# Arduino_HomeMonitorv1r4-current.net
KiCad netlist of a schematic drawn in EAGLE
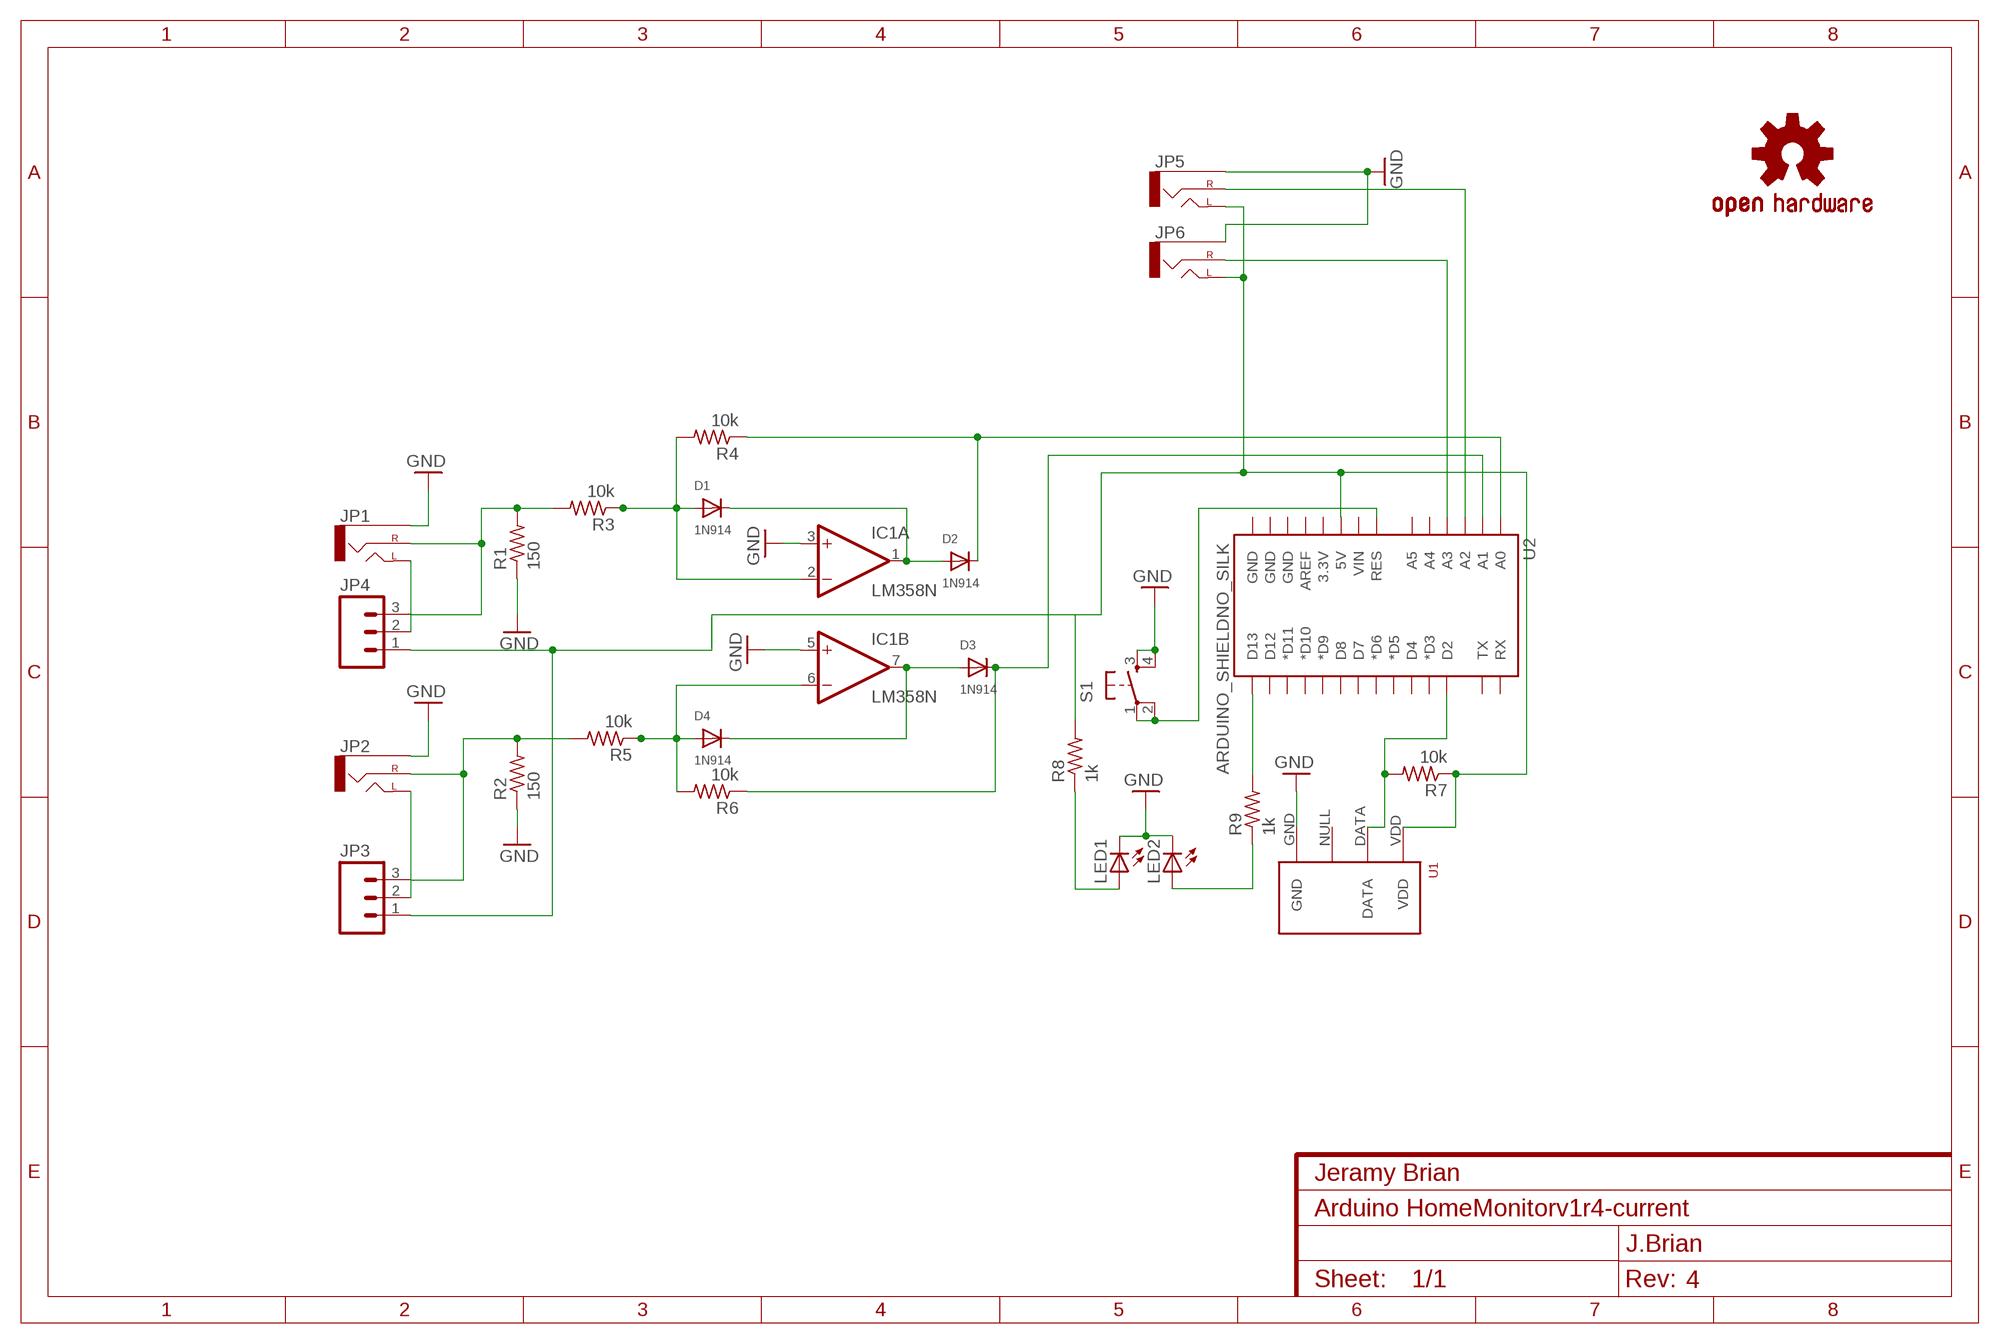
[diagram p0: schematic, sheet 1]

(export (version "E")
  (design (tool "Eeschema 10.0.6"))
  (components
    (comp (ref "D1")
      (value "1N914")
      (footprint "eagle-import:DO-1N4148")
      (libsource (lib "eagle-import") (part "DIODEDO-1N4148"))
    )
    (comp (ref "D2")
      (value "1N914")
      (footprint "eagle-import:DO-1N4148")
      (libsource (lib "eagle-import") (part "DIODEDO-1N4148"))
    )
    (comp (ref "D3")
      (value "1N914")
      (footprint "eagle-import:DO-1N4148")
      (libsource (lib "eagle-import") (part "DIODEDO-1N4148"))
    )
    (comp (ref "D4")
      (value "1N914")
      (footprint "eagle-import:DO-1N4148")
      (libsource (lib "eagle-import") (part "DIODEDO-1N4148"))
    )
    (comp (ref "IC1")
      (value "LM358N")
      (footprint "eagle-import:DIL08")
      (libsource (lib "eagle-import") (part "LM358N"))
    )
    (comp (ref "JP1")
      (value "AUDIO-JACKPTH")
      (footprint "eagle-import:AUDIO-JACK")
      (libsource (lib "eagle-import") (part "AUDIO-JACKPTH"))
    )
    (comp (ref "JP2")
      (value "AUDIO-JACKPTH")
      (footprint "eagle-import:AUDIO-JACK")
      (libsource (lib "eagle-import") (part "AUDIO-JACKPTH"))
    )
    (comp (ref "JP3")
      (value "M03PTH")
      (footprint "eagle-import:1X03")
      (libsource (lib "eagle-import") (part "M03PTH"))
    )
    (comp (ref "JP4")
      (value "M03PTH")
      (footprint "eagle-import:1X03")
      (libsource (lib "eagle-import") (part "M03PTH"))
    )
    (comp (ref "JP5")
      (value "AUDIO-JACKPTH")
      (footprint "eagle-import:AUDIO-JACK")
      (libsource (lib "eagle-import") (part "AUDIO-JACKPTH"))
    )
    (comp (ref "JP6")
      (value "AUDIO-JACKPTH")
      (footprint "eagle-import:AUDIO-JACK")
      (libsource (lib "eagle-import") (part "AUDIO-JACKPTH"))
    )
    (comp (ref "LED1")
      (value "LED3MM")
      (footprint "eagle-import:LED3MM")
      (libsource (lib "eagle-import") (part "LED3MM"))
    )
    (comp (ref "LED2")
      (value "LED3MM")
      (footprint "eagle-import:LED3MM")
      (libsource (lib "eagle-import") (part "LED3MM"))
    )
    (comp (ref "LOGO1")
      (value "OSHW-LOGOL")
      (footprint "eagle-import:OSHW-LOGO-L")
      (libsource (lib "eagle-import") (part "OSHW-LOGOL"))
    )
    (comp (ref "R1")
      (value "150")
      (footprint "eagle-import:R0805")
      (libsource (lib "eagle-import") (part "R-US_R0805"))
    )
    (comp (ref "R2")
      (value "150")
      (footprint "eagle-import:R0805")
      (libsource (lib "eagle-import") (part "R-US_R0805"))
    )
    (comp (ref "R3")
      (value "10k")
      (footprint "eagle-import:R0805")
      (libsource (lib "eagle-import") (part "R-US_R0805"))
    )
    (comp (ref "R4")
      (value "10k")
      (footprint "eagle-import:R0805")
      (libsource (lib "eagle-import") (part "R-US_R0805"))
    )
    (comp (ref "R5")
      (value "10k")
      (footprint "eagle-import:R0805")
      (libsource (lib "eagle-import") (part "R-US_R0805"))
    )
    (comp (ref "R6")
      (value "10k")
      (footprint "eagle-import:R0805")
      (libsource (lib "eagle-import") (part "R-US_R0805"))
    )
    (comp (ref "R7")
      (value "10k")
      (footprint "eagle-import:R0805")
      (libsource (lib "eagle-import") (part "R-US_R0805"))
    )
    (comp (ref "R8")
      (value "1k")
      (footprint "eagle-import:R0805")
      (libsource (lib "eagle-import") (part "R-US_R0805"))
    )
    (comp (ref "R9")
      (value "1k")
      (footprint "eagle-import:R0805")
      (libsource (lib "eagle-import") (part "R-US_R0805"))
    )
    (comp (ref "S1")
      (value "TAC_SWITCHPTH")
      (footprint "eagle-import:TACTILE-PTH")
      (libsource (lib "eagle-import") (part "TAC_SWITCHPTH"))
    )
    (comp (ref "U1")
      (value "RHT03_DHT-22_AM2302")
      (footprint "eagle-import:RHT03_DHT-22")
      (libsource (lib "eagle-import") (part "RHT03_DHT-22_AM2302"))
    )
    (comp (ref "U2")
      (value "ARDUINO_SHIELDNO_SILK")
      (footprint "eagle-import:DUEMILANOVE_VIAS")
      (libsource (lib "eagle-import") (part "ARDUINO_SHIELDNO_SILK"))
    )
  )
  (nets
    (net (code "1") (name "GND") (class "Default")
      (node (ref "IC1") (pin "3") (pinfunction "+IN_3") (pintype "input"))
      (node (ref "IC1") (pin "5") (pinfunction "+IN_5") (pintype "input"))
      (node (ref "JP1") (pin "SLEEVE") (pinfunction "SLEEVE_SLEEVE") (pintype "bidirectional"))
      (node (ref "JP2") (pin "SLEEVE") (pinfunction "SLEEVE_SLEEVE") (pintype "bidirectional"))
      (node (ref "JP5") (pin "SLEEVE") (pinfunction "SLEEVE_SLEEVE") (pintype "bidirectional"))
      (node (ref "JP6") (pin "SLEEVE") (pinfunction "SLEEVE_SLEEVE") (pintype "bidirectional"))
      (node (ref "LED1") (pin "K") (pinfunction "C_K") (pintype "passive"))
      (node (ref "LED2") (pin "K") (pinfunction "C_K") (pintype "passive"))
      (node (ref "R1") (pin "1") (pinfunction "1_1") (pintype "passive"))
      (node (ref "R2") (pin "1") (pinfunction "1_1") (pintype "passive"))
      (node (ref "S1") (pin "3") (pinfunction "3_3") (pintype "passive"))
      (node (ref "S1") (pin "4") (pinfunction "4_4") (pintype "passive"))
      (node (ref "U1") (pin "GND") (pinfunction "GND_GND") (pintype "power_in"))
    )
    (net (code "2") (name "Net-(D2-PadC)") (class "Default")
      (node (ref "D2") (pin "C") (pinfunction "C_C") (pintype "passive"))
      (node (ref "R4") (pin "1") (pinfunction "1_1") (pintype "passive"))
      (node (ref "U2") (pin "A0") (pinfunction "A0_A0") (pintype "bidirectional"))
    )
    (net (code "3") (name "Net-(D3-PadC)") (class "Default")
      (node (ref "D3") (pin "C") (pinfunction "C_C") (pintype "passive"))
      (node (ref "R6") (pin "1") (pinfunction "1_1") (pintype "passive"))
      (node (ref "U2") (pin "A1") (pinfunction "A1_A1") (pintype "bidirectional"))
    )
    (net (code "4") (name "Net-(IC1A--IN)") (class "Default")
      (node (ref "D1") (pin "A") (pinfunction "A_A") (pintype "passive"))
      (node (ref "IC1") (pin "2") (pinfunction "-IN_2") (pintype "input"))
      (node (ref "R3") (pin "1") (pinfunction "1_1") (pintype "passive"))
      (node (ref "R4") (pin "2") (pinfunction "2_2") (pintype "passive"))
    )
    (net (code "5") (name "Net-(IC1A-OUT)") (class "Default")
      (node (ref "D1") (pin "C") (pinfunction "C_C") (pintype "passive"))
      (node (ref "D2") (pin "A") (pinfunction "A_A") (pintype "passive"))
      (node (ref "IC1") (pin "1") (pinfunction "OUT_1") (pintype "output"))
    )
    (net (code "6") (name "Net-(IC1B--IN)") (class "Default")
      (node (ref "D4") (pin "A") (pinfunction "A_A") (pintype "passive"))
      (node (ref "IC1") (pin "6") (pinfunction "-IN_6") (pintype "input"))
      (node (ref "R5") (pin "1") (pinfunction "1_1") (pintype "passive"))
      (node (ref "R6") (pin "2") (pinfunction "2_2") (pintype "passive"))
    )
    (net (code "7") (name "Net-(IC1B-OUT)") (class "Default")
      (node (ref "D3") (pin "A") (pinfunction "A_A") (pintype "passive"))
      (node (ref "D4") (pin "C") (pinfunction "C_C") (pintype "passive"))
      (node (ref "IC1") (pin "7") (pinfunction "OUT_7") (pintype "output"))
    )
    (net (code "8") (name "Net-(JP1-LEFT)") (class "Default")
      (node (ref "JP1") (pin "TIP") (pinfunction "LEFT_TIP") (pintype "bidirectional"))
      (node (ref "JP4") (pin "2") (pinfunction "2_2") (pintype "passive"))
    )
    (net (code "9") (name "Net-(JP1-RIGHT)") (class "Default")
      (node (ref "JP1") (pin "RING") (pinfunction "RIGHT_RING") (pintype "bidirectional"))
      (node (ref "JP4") (pin "3") (pinfunction "3_3") (pintype "passive"))
      (node (ref "R1") (pin "2") (pinfunction "2_2") (pintype "passive"))
      (node (ref "R3") (pin "2") (pinfunction "2_2") (pintype "passive"))
    )
    (net (code "10") (name "Net-(JP2-LEFT)") (class "Default")
      (node (ref "JP2") (pin "TIP") (pinfunction "LEFT_TIP") (pintype "bidirectional"))
      (node (ref "JP3") (pin "2") (pinfunction "2_2") (pintype "passive"))
    )
    (net (code "11") (name "Net-(JP2-RIGHT)") (class "Default")
      (node (ref "JP2") (pin "RING") (pinfunction "RIGHT_RING") (pintype "bidirectional"))
      (node (ref "JP3") (pin "3") (pinfunction "3_3") (pintype "passive"))
      (node (ref "R2") (pin "2") (pinfunction "2_2") (pintype "passive"))
      (node (ref "R5") (pin "2") (pinfunction "2_2") (pintype "passive"))
    )
    (net (code "12") (name "Net-(JP5-LEFT)") (class "Default")
      (node (ref "JP3") (pin "1") (pinfunction "1_1") (pintype "passive"))
      (node (ref "JP4") (pin "1") (pinfunction "1_1") (pintype "passive"))
      (node (ref "JP5") (pin "TIP") (pinfunction "LEFT_TIP") (pintype "bidirectional"))
      (node (ref "JP6") (pin "TIP") (pinfunction "LEFT_TIP") (pintype "bidirectional"))
      (node (ref "R7") (pin "1") (pinfunction "1_1") (pintype "passive"))
      (node (ref "R8") (pin "2") (pinfunction "2_2") (pintype "passive"))
      (node (ref "U1") (pin "VDD") (pinfunction "VDD_VDD") (pintype "power_in"))
      (node (ref "U2") (pin "5V") (pinfunction "5V_5V") (pintype "bidirectional"))
    )
    (net (code "13") (name "Net-(JP5-RIGHT)") (class "Default")
      (node (ref "JP5") (pin "RING") (pinfunction "RIGHT_RING") (pintype "bidirectional"))
      (node (ref "U2") (pin "A2") (pinfunction "A2_A2") (pintype "bidirectional"))
    )
    (net (code "14") (name "Net-(JP6-RIGHT)") (class "Default")
      (node (ref "JP6") (pin "RING") (pinfunction "RIGHT_RING") (pintype "bidirectional"))
      (node (ref "U2") (pin "A3") (pinfunction "A3_A3") (pintype "bidirectional"))
    )
    (net (code "15") (name "Net-(LED1-PadA)") (class "Default")
      (node (ref "LED1") (pin "A") (pinfunction "A_A") (pintype "passive"))
      (node (ref "R8") (pin "1") (pinfunction "1_1") (pintype "passive"))
    )
    (net (code "16") (name "Net-(LED2-PadA)") (class "Default")
      (node (ref "LED2") (pin "A") (pinfunction "A_A") (pintype "passive"))
      (node (ref "R9") (pin "1") (pinfunction "1_1") (pintype "passive"))
    )
    (net (code "17") (name "Net-(R7-Pad2)") (class "Default")
      (node (ref "R7") (pin "2") (pinfunction "2_2") (pintype "passive"))
      (node (ref "U1") (pin "DATA") (pinfunction "DATA_DATA") (pintype "bidirectional"))
      (node (ref "U2") (pin "D2") (pinfunction "D2_D2") (pintype "bidirectional"))
    )
    (net (code "18") (name "Net-(R9-Pad2)") (class "Default")
      (node (ref "R9") (pin "2") (pinfunction "2_2") (pintype "passive"))
      (node (ref "U2") (pin "D13") (pinfunction "D13_D13") (pintype "bidirectional"))
    )
    (net (code "19") (name "Net-(S1-Pad1)") (class "Default")
      (node (ref "S1") (pin "1") (pinfunction "1_1") (pintype "passive"))
      (node (ref "S1") (pin "2") (pinfunction "2_2") (pintype "passive"))
      (node (ref "U2") (pin "RES") (pinfunction "RES_RES") (pintype "bidirectional"))
    )
    (net (code "20") (name "unconnected-(U1-PadNULL)") (class "Default")
      (node (ref "U1") (pin "NULL") (pinfunction "NULL_NULL") (pintype "no_connect"))
    )
    (net (code "21") (name "unconnected-(U2-*D3-PadD3)") (class "Default")
      (node (ref "U2") (pin "D3") (pinfunction "*D3_D3") (pintype "bidirectional"))
    )
    (net (code "22") (name "unconnected-(U2-*D5-PadD5)") (class "Default")
      (node (ref "U2") (pin "D5") (pinfunction "*D5_D5") (pintype "bidirectional"))
    )
    (net (code "23") (name "unconnected-(U2-*D6-PadD6)") (class "Default")
      (node (ref "U2") (pin "D6") (pinfunction "*D6_D6") (pintype "bidirectional"))
    )
    (net (code "24") (name "unconnected-(U2-*D9-PadD9)") (class "Default")
      (node (ref "U2") (pin "D9") (pinfunction "*D9_D9") (pintype "bidirectional"))
    )
    (net (code "25") (name "unconnected-(U2-*D10-PadD10)") (class "Default")
      (node (ref "U2") (pin "D10") (pinfunction "*D10_D10") (pintype "bidirectional"))
    )
    (net (code "26") (name "unconnected-(U2-*D11-PadD11)") (class "Default")
      (node (ref "U2") (pin "D11") (pinfunction "*D11_D11") (pintype "bidirectional"))
    )
    (net (code "27") (name "unconnected-(U2-GND-PadGND@0)") (class "Default")
      (node (ref "U2") (pin "GND@0") (pinfunction "GND_GND@0") (pintype "bidirectional"))
    )
    (net (code "28") (name "unconnected-(U2-GND-PadGND@1)") (class "Default")
      (node (ref "U2") (pin "GND@1") (pinfunction "GND_GND@1") (pintype "bidirectional"))
    )
    (net (code "29") (name "unconnected-(U2-GND-PadGND@2)") (class "Default")
      (node (ref "U2") (pin "GND@2") (pinfunction "GND_GND@2") (pintype "bidirectional"))
    )
    (net (code "30") (name "unconnected-(U2-Pad3.3V)") (class "Default")
      (node (ref "U2") (pin "3.3V") (pinfunction "3.3V_3.3V") (pintype "bidirectional"))
    )
    (net (code "31") (name "unconnected-(U2-PadA4)") (class "Default")
      (node (ref "U2") (pin "A4") (pinfunction "A4_A4") (pintype "bidirectional"))
    )
    (net (code "32") (name "unconnected-(U2-PadA5)") (class "Default")
      (node (ref "U2") (pin "A5") (pinfunction "A5_A5") (pintype "bidirectional"))
    )
    (net (code "33") (name "unconnected-(U2-PadAREF)") (class "Default")
      (node (ref "U2") (pin "AREF") (pinfunction "AREF_AREF") (pintype "bidirectional"))
    )
    (net (code "34") (name "unconnected-(U2-PadD4)") (class "Default")
      (node (ref "U2") (pin "D4") (pinfunction "D4_D4") (pintype "bidirectional"))
    )
    (net (code "35") (name "unconnected-(U2-PadD7)") (class "Default")
      (node (ref "U2") (pin "D7") (pinfunction "D7_D7") (pintype "bidirectional"))
    )
    (net (code "36") (name "unconnected-(U2-PadD8)") (class "Default")
      (node (ref "U2") (pin "D8") (pinfunction "D8_D8") (pintype "bidirectional"))
    )
    (net (code "37") (name "unconnected-(U2-PadD12)") (class "Default")
      (node (ref "U2") (pin "D12") (pinfunction "D12_D12") (pintype "bidirectional"))
    )
    (net (code "38") (name "unconnected-(U2-PadRX)") (class "Default")
      (node (ref "U2") (pin "RX") (pinfunction "RX_RX") (pintype "bidirectional"))
    )
    (net (code "39") (name "unconnected-(U2-PadTX)") (class "Default")
      (node (ref "U2") (pin "TX") (pinfunction "TX_TX") (pintype "bidirectional"))
    )
    (net (code "40") (name "unconnected-(U2-PadVIN)") (class "Default")
      (node (ref "U2") (pin "VIN") (pinfunction "VIN_VIN") (pintype "bidirectional"))
    )
  )
)
